# Mic_Preamp.net
KiCad netlist of a schematic drawn in EAGLE
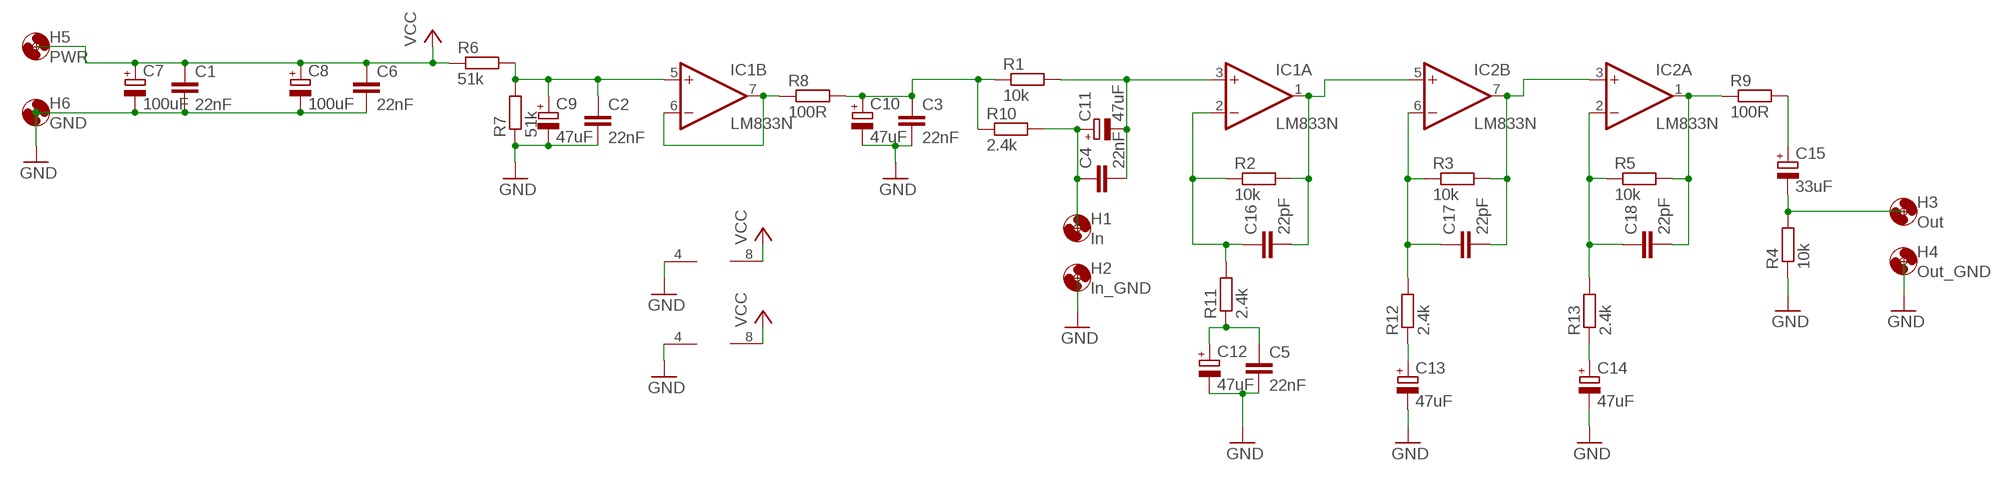
[diagram p0: schematic, sheet 1]

(export (version "E")
  (design (tool "Eeschema 10.0.6"))
  (components
    (comp (ref "C1")
      (value "22nF")
      (footprint "eagle-import:C050-025X075")
      (libsource (lib "eagle-import") (part "C-EU050-025X075"))
    )
    (comp (ref "C2")
      (value "22nF")
      (footprint "eagle-import:C050-025X075")
      (libsource (lib "eagle-import") (part "C-EU050-025X075"))
    )
    (comp (ref "C3")
      (value "22nF")
      (footprint "eagle-import:C050-025X075")
      (libsource (lib "eagle-import") (part "C-EU050-025X075"))
    )
    (comp (ref "C4")
      (value "22nF")
      (footprint "eagle-import:C050-025X075")
      (libsource (lib "eagle-import") (part "C-EU050-025X075"))
    )
    (comp (ref "C5")
      (value "22nF")
      (footprint "eagle-import:C050-025X075")
      (libsource (lib "eagle-import") (part "C-EU050-025X075"))
    )
    (comp (ref "C6")
      (value "22nF")
      (footprint "eagle-import:C050-025X075")
      (libsource (lib "eagle-import") (part "C-EU050-025X075"))
    )
    (comp (ref "C7")
      (value "100uF")
      (footprint "eagle-import:C_6032-28R")
      (libsource (lib "eagle-import") (part "CPOL-EUC/6032-28R"))
    )
    (comp (ref "C8")
      (value "100uF")
      (footprint "eagle-import:C_6032-28R")
      (libsource (lib "eagle-import") (part "CPOL-EUC/6032-28R"))
    )
    (comp (ref "C9")
      (value "47uF")
      (footprint "eagle-import:E2,5-5")
      (libsource (lib "eagle-import") (part "CPOL-EUE2.5-5"))
    )
    (comp (ref "C10")
      (value "47uF")
      (footprint "eagle-import:E2,5-5")
      (libsource (lib "eagle-import") (part "CPOL-EUE2.5-5"))
    )
    (comp (ref "C11")
      (value "47uF")
      (footprint "eagle-import:E2,5-5")
      (libsource (lib "eagle-import") (part "CPOL-EUE2.5-5"))
    )
    (comp (ref "C12")
      (value "47uF")
      (footprint "eagle-import:E2,5-5")
      (libsource (lib "eagle-import") (part "CPOL-EUE2.5-5"))
    )
    (comp (ref "C13")
      (value "47uF")
      (footprint "eagle-import:E2,5-5")
      (libsource (lib "eagle-import") (part "CPOL-EUE2.5-5"))
    )
    (comp (ref "C14")
      (value "47uF")
      (footprint "eagle-import:E2,5-5")
      (libsource (lib "eagle-import") (part "CPOL-EUE2.5-5"))
    )
    (comp (ref "C15")
      (value "33uF")
      (footprint "eagle-import:E2,5-5")
      (libsource (lib "eagle-import") (part "CPOL-EUE2.5-5"))
    )
    (comp (ref "C16")
      (value "22pF")
      (footprint "eagle-import:C0603K")
      (libsource (lib "eagle-import") (part "C-EUC0603K"))
    )
    (comp (ref "C17")
      (value "22pF")
      (footprint "eagle-import:C0603K")
      (libsource (lib "eagle-import") (part "C-EUC0603K"))
    )
    (comp (ref "C18")
      (value "22pF")
      (footprint "eagle-import:C0603K")
      (libsource (lib "eagle-import") (part "C-EUC0603K"))
    )
    (comp (ref "H1")
      (value "In")
      (footprint "eagle-import:3,0")
      (libsource (lib "eagle-import") (part "MOUNT-HOLE3.0"))
    )
    (comp (ref "H2")
      (value "In_GND")
      (footprint "eagle-import:3,0")
      (libsource (lib "eagle-import") (part "MOUNT-HOLE3.0"))
    )
    (comp (ref "H3")
      (value "Out")
      (footprint "eagle-import:3,0")
      (libsource (lib "eagle-import") (part "MOUNT-HOLE3.0"))
    )
    (comp (ref "H4")
      (value "Out_GND")
      (footprint "eagle-import:3,0")
      (libsource (lib "eagle-import") (part "MOUNT-HOLE3.0"))
    )
    (comp (ref "H5")
      (value "PWR")
      (footprint "eagle-import:3,0")
      (libsource (lib "eagle-import") (part "MOUNT-HOLE3.0"))
    )
    (comp (ref "H6")
      (value "GND")
      (footprint "eagle-import:3,0")
      (libsource (lib "eagle-import") (part "MOUNT-HOLE3.0"))
    )
    (comp (ref "IC1")
      (value "LM833N")
      (footprint "eagle-import:DIL08")
      (libsource (lib "eagle-import") (part "LM833N"))
    )
    (comp (ref "IC2")
      (value "LM833N")
      (footprint "eagle-import:DIL08")
      (libsource (lib "eagle-import") (part "LM833N"))
    )
    (comp (ref "R1")
      (value "10k")
      (footprint "eagle-import:R0805")
      (libsource (lib "eagle-import") (part "R-EU_R0805"))
    )
    (comp (ref "R2")
      (value "10k")
      (footprint "eagle-import:R0805")
      (libsource (lib "eagle-import") (part "R-EU_R0805"))
    )
    (comp (ref "R3")
      (value "10k")
      (footprint "eagle-import:R0805")
      (libsource (lib "eagle-import") (part "R-EU_R0805"))
    )
    (comp (ref "R4")
      (value "10k")
      (footprint "eagle-import:R0805")
      (libsource (lib "eagle-import") (part "R-EU_R0805"))
    )
    (comp (ref "R5")
      (value "10k")
      (footprint "eagle-import:R0805")
      (libsource (lib "eagle-import") (part "R-EU_R0805"))
    )
    (comp (ref "R6")
      (value "51k")
      (footprint "eagle-import:R0805")
      (libsource (lib "eagle-import") (part "R-EU_R0805"))
    )
    (comp (ref "R7")
      (value "51k")
      (footprint "eagle-import:R0805")
      (libsource (lib "eagle-import") (part "R-EU_R0805"))
    )
    (comp (ref "R8")
      (value "100R")
      (footprint "eagle-import:R0805")
      (libsource (lib "eagle-import") (part "R-EU_R0805"))
    )
    (comp (ref "R9")
      (value "100R")
      (footprint "eagle-import:R0805")
      (libsource (lib "eagle-import") (part "R-EU_R0805"))
    )
    (comp (ref "R10")
      (value "2.4k")
      (footprint "eagle-import:R0805")
      (libsource (lib "eagle-import") (part "R-EU_R0805"))
    )
    (comp (ref "R11")
      (value "2.4k")
      (footprint "eagle-import:R0805")
      (libsource (lib "eagle-import") (part "R-EU_R0805"))
    )
    (comp (ref "R12")
      (value "2.4k")
      (footprint "eagle-import:R0805")
      (libsource (lib "eagle-import") (part "R-EU_R0805"))
    )
    (comp (ref "R13")
      (value "2.4k")
      (footprint "eagle-import:R0805")
      (libsource (lib "eagle-import") (part "R-EU_R0805"))
    )
  )
  (nets
    (net (code "1") (name "GND") (class "Default")
      (node (ref "C1") (pin "2") (pinfunction "2_2") (pintype "passive"))
      (node (ref "C10") (pin "-") (pinfunction "-_-") (pintype "passive"))
      (node (ref "C12") (pin "-") (pinfunction "-_-") (pintype "passive"))
      (node (ref "C13") (pin "-") (pinfunction "-_-") (pintype "passive"))
      (node (ref "C14") (pin "-") (pinfunction "-_-") (pintype "passive"))
      (node (ref "C2") (pin "2") (pinfunction "2_2") (pintype "passive"))
      (node (ref "C3") (pin "2") (pinfunction "2_2") (pintype "passive"))
      (node (ref "C5") (pin "2") (pinfunction "2_2") (pintype "passive"))
      (node (ref "C6") (pin "2") (pinfunction "2_2") (pintype "passive"))
      (node (ref "C7") (pin "-") (pinfunction "-_-") (pintype "passive"))
      (node (ref "C8") (pin "-") (pinfunction "-_-") (pintype "passive"))
      (node (ref "C9") (pin "-") (pinfunction "-_-") (pintype "passive"))
      (node (ref "H2") (pin "P$1") (pinfunction "P$1_P$1") (pintype "bidirectional"))
      (node (ref "H4") (pin "P$1") (pinfunction "P$1_P$1") (pintype "bidirectional"))
      (node (ref "H6") (pin "P$1") (pinfunction "P$1_P$1") (pintype "bidirectional"))
      (node (ref "IC1") (pin "4") (pinfunction "V-_4") (pintype "power_in"))
      (node (ref "IC2") (pin "4") (pinfunction "V-_4") (pintype "power_in"))
      (node (ref "R4") (pin "1") (pinfunction "1_1") (pintype "passive"))
      (node (ref "R7") (pin "1") (pinfunction "1_1") (pintype "passive"))
    )
    (net (code "2") (name "Net-(C10-Pad+)") (class "Default")
      (node (ref "C10") (pin "+") (pinfunction "+_+") (pintype "passive"))
      (node (ref "C3") (pin "1") (pinfunction "1_1") (pintype "passive"))
      (node (ref "R1") (pin "1") (pinfunction "1_1") (pintype "passive"))
      (node (ref "R10") (pin "1") (pinfunction "1_1") (pintype "passive"))
      (node (ref "R8") (pin "2") (pinfunction "2_2") (pintype "passive"))
    )
    (net (code "3") (name "Net-(C11-Pad+)") (class "Default")
      (node (ref "C11") (pin "+") (pinfunction "+_+") (pintype "passive"))
      (node (ref "C4") (pin "1") (pinfunction "1_1") (pintype "passive"))
      (node (ref "H1") (pin "P$1") (pinfunction "P$1_P$1") (pintype "bidirectional"))
      (node (ref "R10") (pin "2") (pinfunction "2_2") (pintype "passive"))
    )
    (net (code "4") (name "Net-(C12-Pad+)") (class "Default")
      (node (ref "C12") (pin "+") (pinfunction "+_+") (pintype "passive"))
      (node (ref "C5") (pin "1") (pinfunction "1_1") (pintype "passive"))
      (node (ref "R11") (pin "1") (pinfunction "1_1") (pintype "passive"))
    )
    (net (code "5") (name "Net-(C13-Pad+)") (class "Default")
      (node (ref "C13") (pin "+") (pinfunction "+_+") (pintype "passive"))
      (node (ref "R12") (pin "1") (pinfunction "1_1") (pintype "passive"))
    )
    (net (code "6") (name "Net-(C14-Pad+)") (class "Default")
      (node (ref "C14") (pin "+") (pinfunction "+_+") (pintype "passive"))
      (node (ref "R13") (pin "1") (pinfunction "1_1") (pintype "passive"))
    )
    (net (code "7") (name "Net-(C15-Pad+)") (class "Default")
      (node (ref "C15") (pin "+") (pinfunction "+_+") (pintype "passive"))
      (node (ref "R9") (pin "2") (pinfunction "2_2") (pintype "passive"))
    )
    (net (code "8") (name "Net-(C15-Pad-)") (class "Default")
      (node (ref "C15") (pin "-") (pinfunction "-_-") (pintype "passive"))
      (node (ref "H3") (pin "P$1") (pinfunction "P$1_P$1") (pintype "bidirectional"))
      (node (ref "R4") (pin "2") (pinfunction "2_2") (pintype "passive"))
    )
    (net (code "9") (name "Net-(IC1A-+IN)") (class "Default")
      (node (ref "C11") (pin "-") (pinfunction "-_-") (pintype "passive"))
      (node (ref "C4") (pin "2") (pinfunction "2_2") (pintype "passive"))
      (node (ref "IC1") (pin "3") (pinfunction "+IN_3") (pintype "input"))
      (node (ref "R1") (pin "2") (pinfunction "2_2") (pintype "passive"))
    )
    (net (code "10") (name "Net-(IC1A--IN)") (class "Default")
      (node (ref "C16") (pin "1") (pinfunction "1_1") (pintype "passive"))
      (node (ref "IC1") (pin "2") (pinfunction "-IN_2") (pintype "input"))
      (node (ref "R11") (pin "2") (pinfunction "2_2") (pintype "passive"))
      (node (ref "R2") (pin "1") (pinfunction "1_1") (pintype "passive"))
    )
    (net (code "11") (name "Net-(IC1A-OUT)") (class "Default")
      (node (ref "C16") (pin "2") (pinfunction "2_2") (pintype "passive"))
      (node (ref "IC1") (pin "1") (pinfunction "OUT_1") (pintype "output"))
      (node (ref "IC2") (pin "5") (pinfunction "+IN_5") (pintype "input"))
      (node (ref "R2") (pin "2") (pinfunction "2_2") (pintype "passive"))
    )
    (net (code "12") (name "Net-(IC1B-+IN)") (class "Default")
      (node (ref "C2") (pin "1") (pinfunction "1_1") (pintype "passive"))
      (node (ref "C9") (pin "+") (pinfunction "+_+") (pintype "passive"))
      (node (ref "IC1") (pin "5") (pinfunction "+IN_5") (pintype "input"))
      (node (ref "R6") (pin "2") (pinfunction "2_2") (pintype "passive"))
      (node (ref "R7") (pin "2") (pinfunction "2_2") (pintype "passive"))
    )
    (net (code "13") (name "Net-(IC1B--IN)") (class "Default")
      (node (ref "IC1") (pin "6") (pinfunction "-IN_6") (pintype "input"))
      (node (ref "IC1") (pin "7") (pinfunction "OUT_7") (pintype "output"))
      (node (ref "R8") (pin "1") (pinfunction "1_1") (pintype "passive"))
    )
    (net (code "14") (name "Net-(IC2A-+IN)") (class "Default")
      (node (ref "C17") (pin "2") (pinfunction "2_2") (pintype "passive"))
      (node (ref "IC2") (pin "3") (pinfunction "+IN_3") (pintype "input"))
      (node (ref "IC2") (pin "7") (pinfunction "OUT_7") (pintype "output"))
      (node (ref "R3") (pin "2") (pinfunction "2_2") (pintype "passive"))
    )
    (net (code "15") (name "Net-(IC2A--IN)") (class "Default")
      (node (ref "C18") (pin "1") (pinfunction "1_1") (pintype "passive"))
      (node (ref "IC2") (pin "2") (pinfunction "-IN_2") (pintype "input"))
      (node (ref "R13") (pin "2") (pinfunction "2_2") (pintype "passive"))
      (node (ref "R5") (pin "1") (pinfunction "1_1") (pintype "passive"))
    )
    (net (code "16") (name "Net-(IC2A-OUT)") (class "Default")
      (node (ref "C18") (pin "2") (pinfunction "2_2") (pintype "passive"))
      (node (ref "IC2") (pin "1") (pinfunction "OUT_1") (pintype "output"))
      (node (ref "R5") (pin "2") (pinfunction "2_2") (pintype "passive"))
      (node (ref "R9") (pin "1") (pinfunction "1_1") (pintype "passive"))
    )
    (net (code "17") (name "Net-(IC2B--IN)") (class "Default")
      (node (ref "C17") (pin "1") (pinfunction "1_1") (pintype "passive"))
      (node (ref "IC2") (pin "6") (pinfunction "-IN_6") (pintype "input"))
      (node (ref "R12") (pin "2") (pinfunction "2_2") (pintype "passive"))
      (node (ref "R3") (pin "1") (pinfunction "1_1") (pintype "passive"))
    )
    (net (code "18") (name "VCC") (class "Default")
      (node (ref "C1") (pin "1") (pinfunction "1_1") (pintype "passive"))
      (node (ref "C6") (pin "1") (pinfunction "1_1") (pintype "passive"))
      (node (ref "C7") (pin "+") (pinfunction "+_+") (pintype "passive"))
      (node (ref "C8") (pin "+") (pinfunction "+_+") (pintype "passive"))
      (node (ref "H5") (pin "P$1") (pinfunction "P$1_P$1") (pintype "bidirectional"))
      (node (ref "IC1") (pin "8") (pinfunction "V+_8") (pintype "power_in"))
      (node (ref "IC2") (pin "8") (pinfunction "V+_8") (pintype "power_in"))
      (node (ref "R6") (pin "1") (pinfunction "1_1") (pintype "passive"))
    )
  )
)
